# lightSource.net
KiCad netlist of a schematic drawn in EAGLE
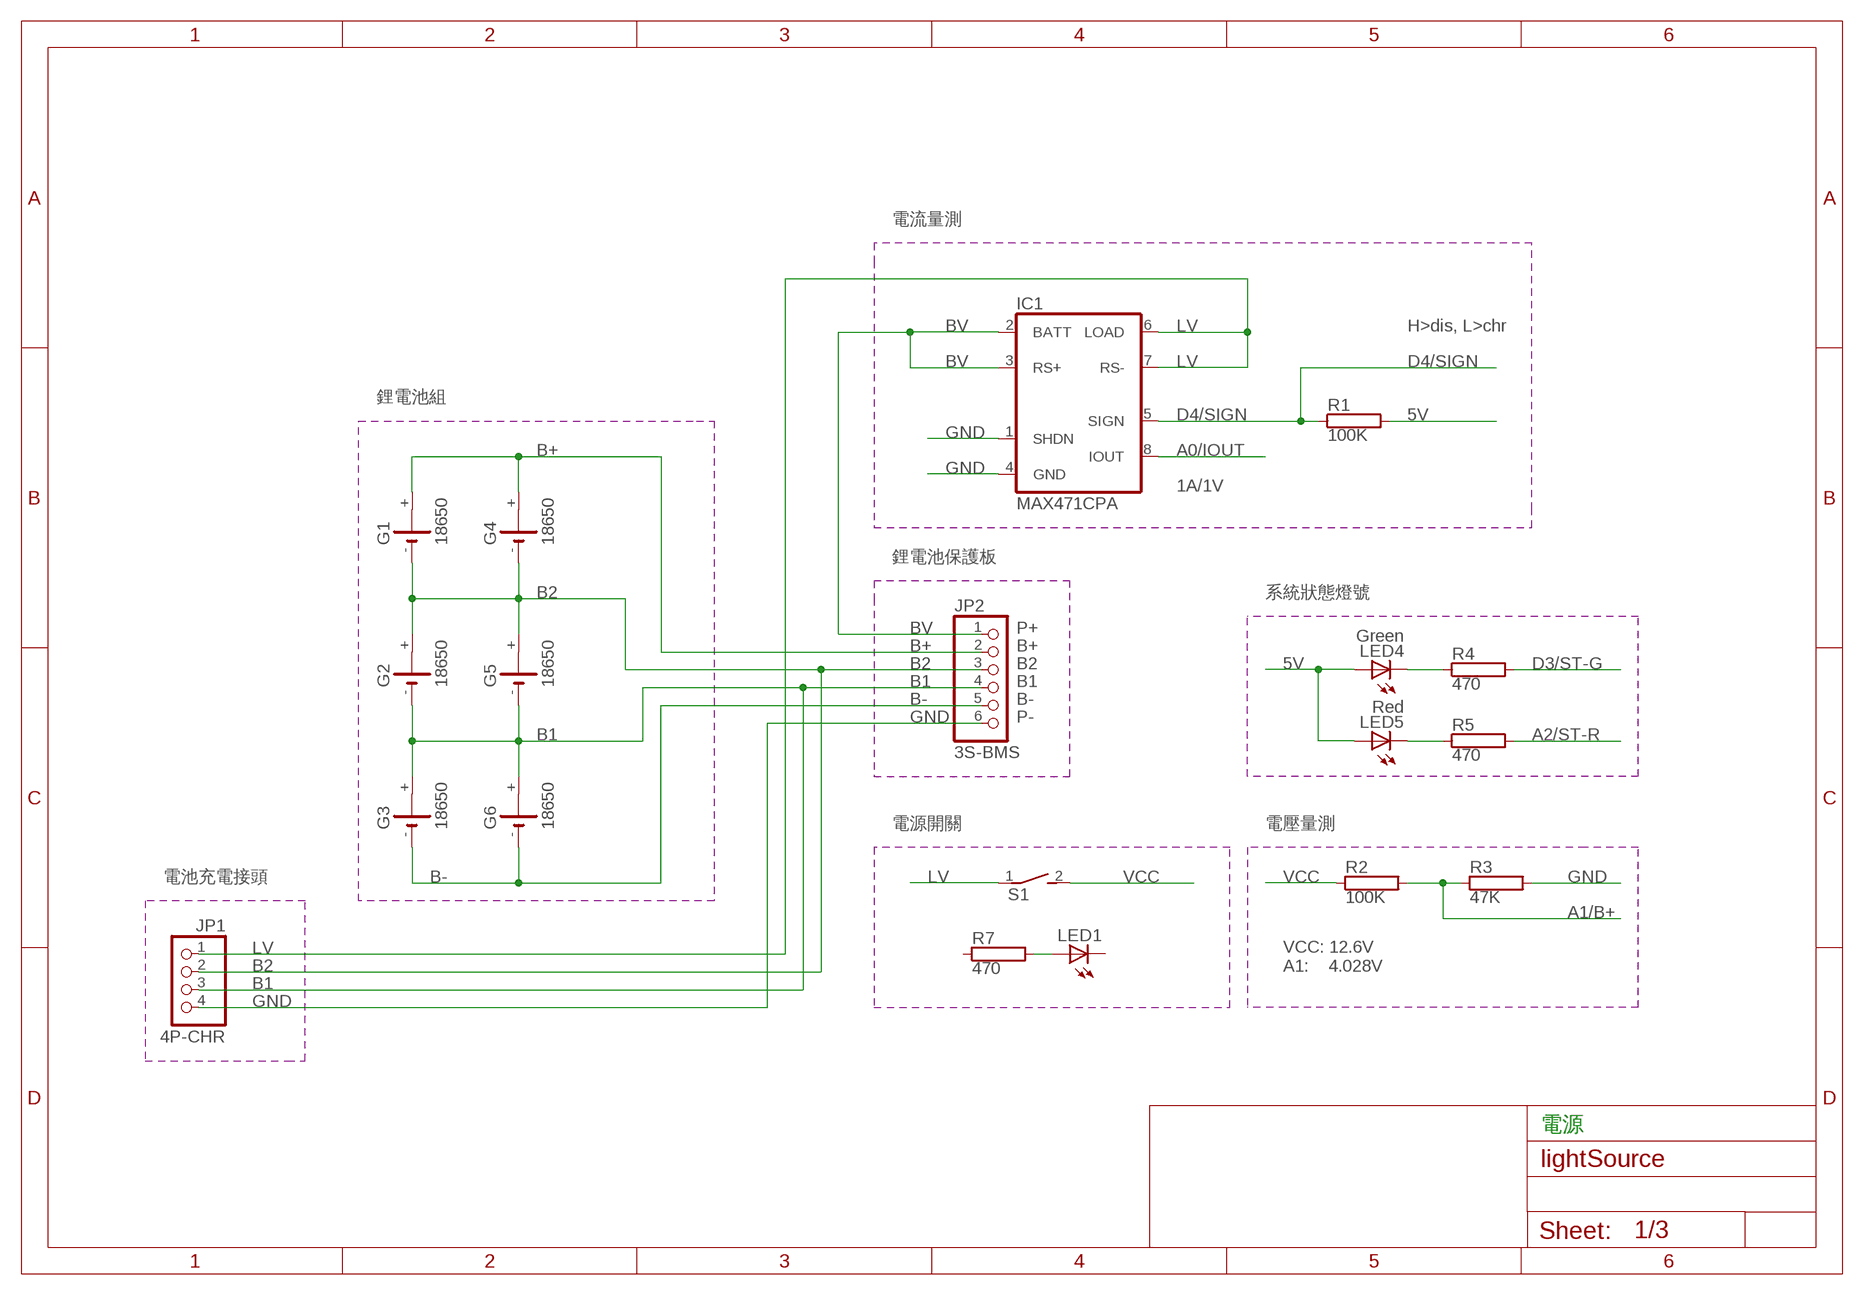
[diagram p0: schematic, sheet 1]
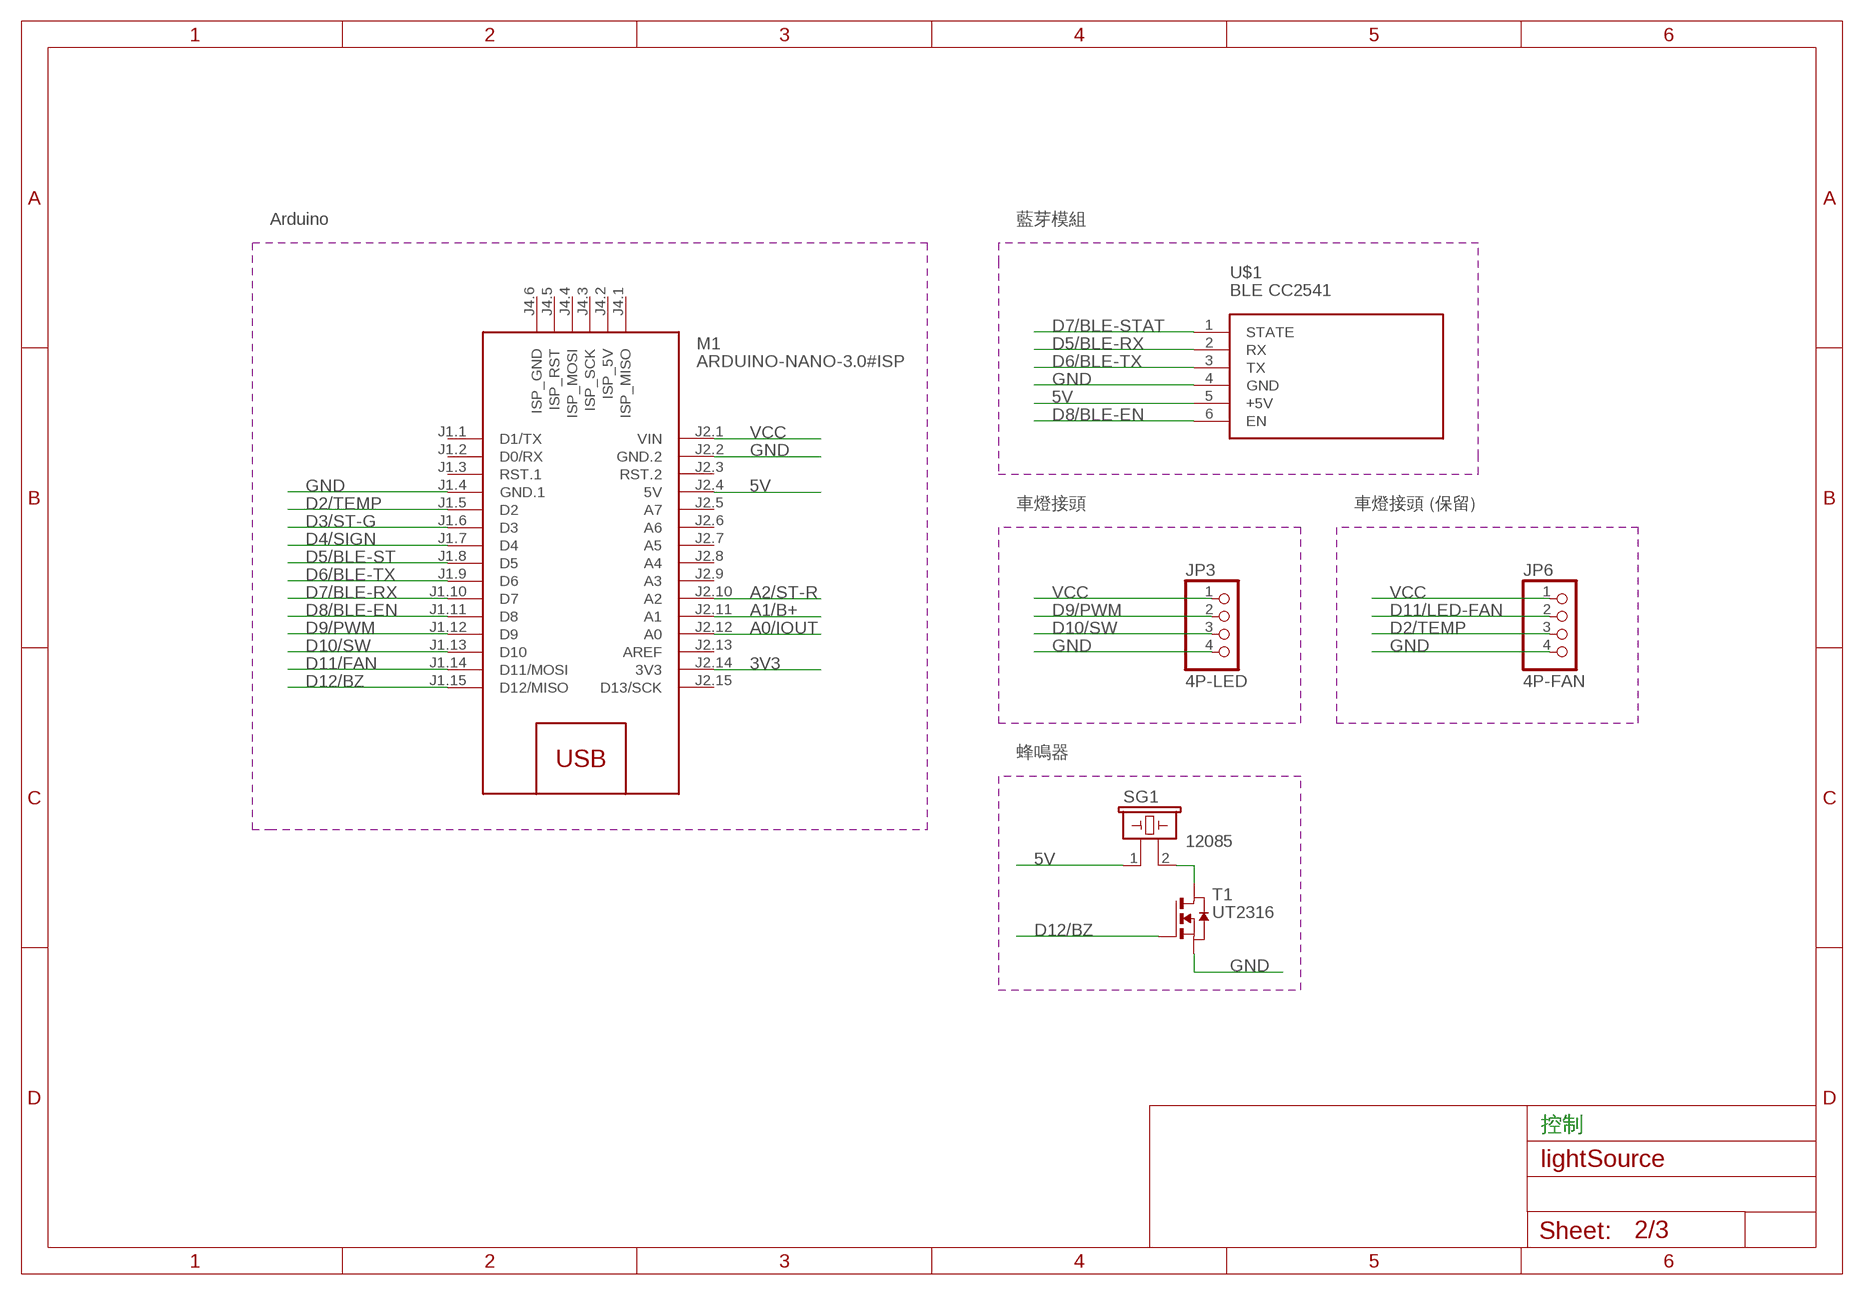
[diagram p1: schematic, sheet 2]
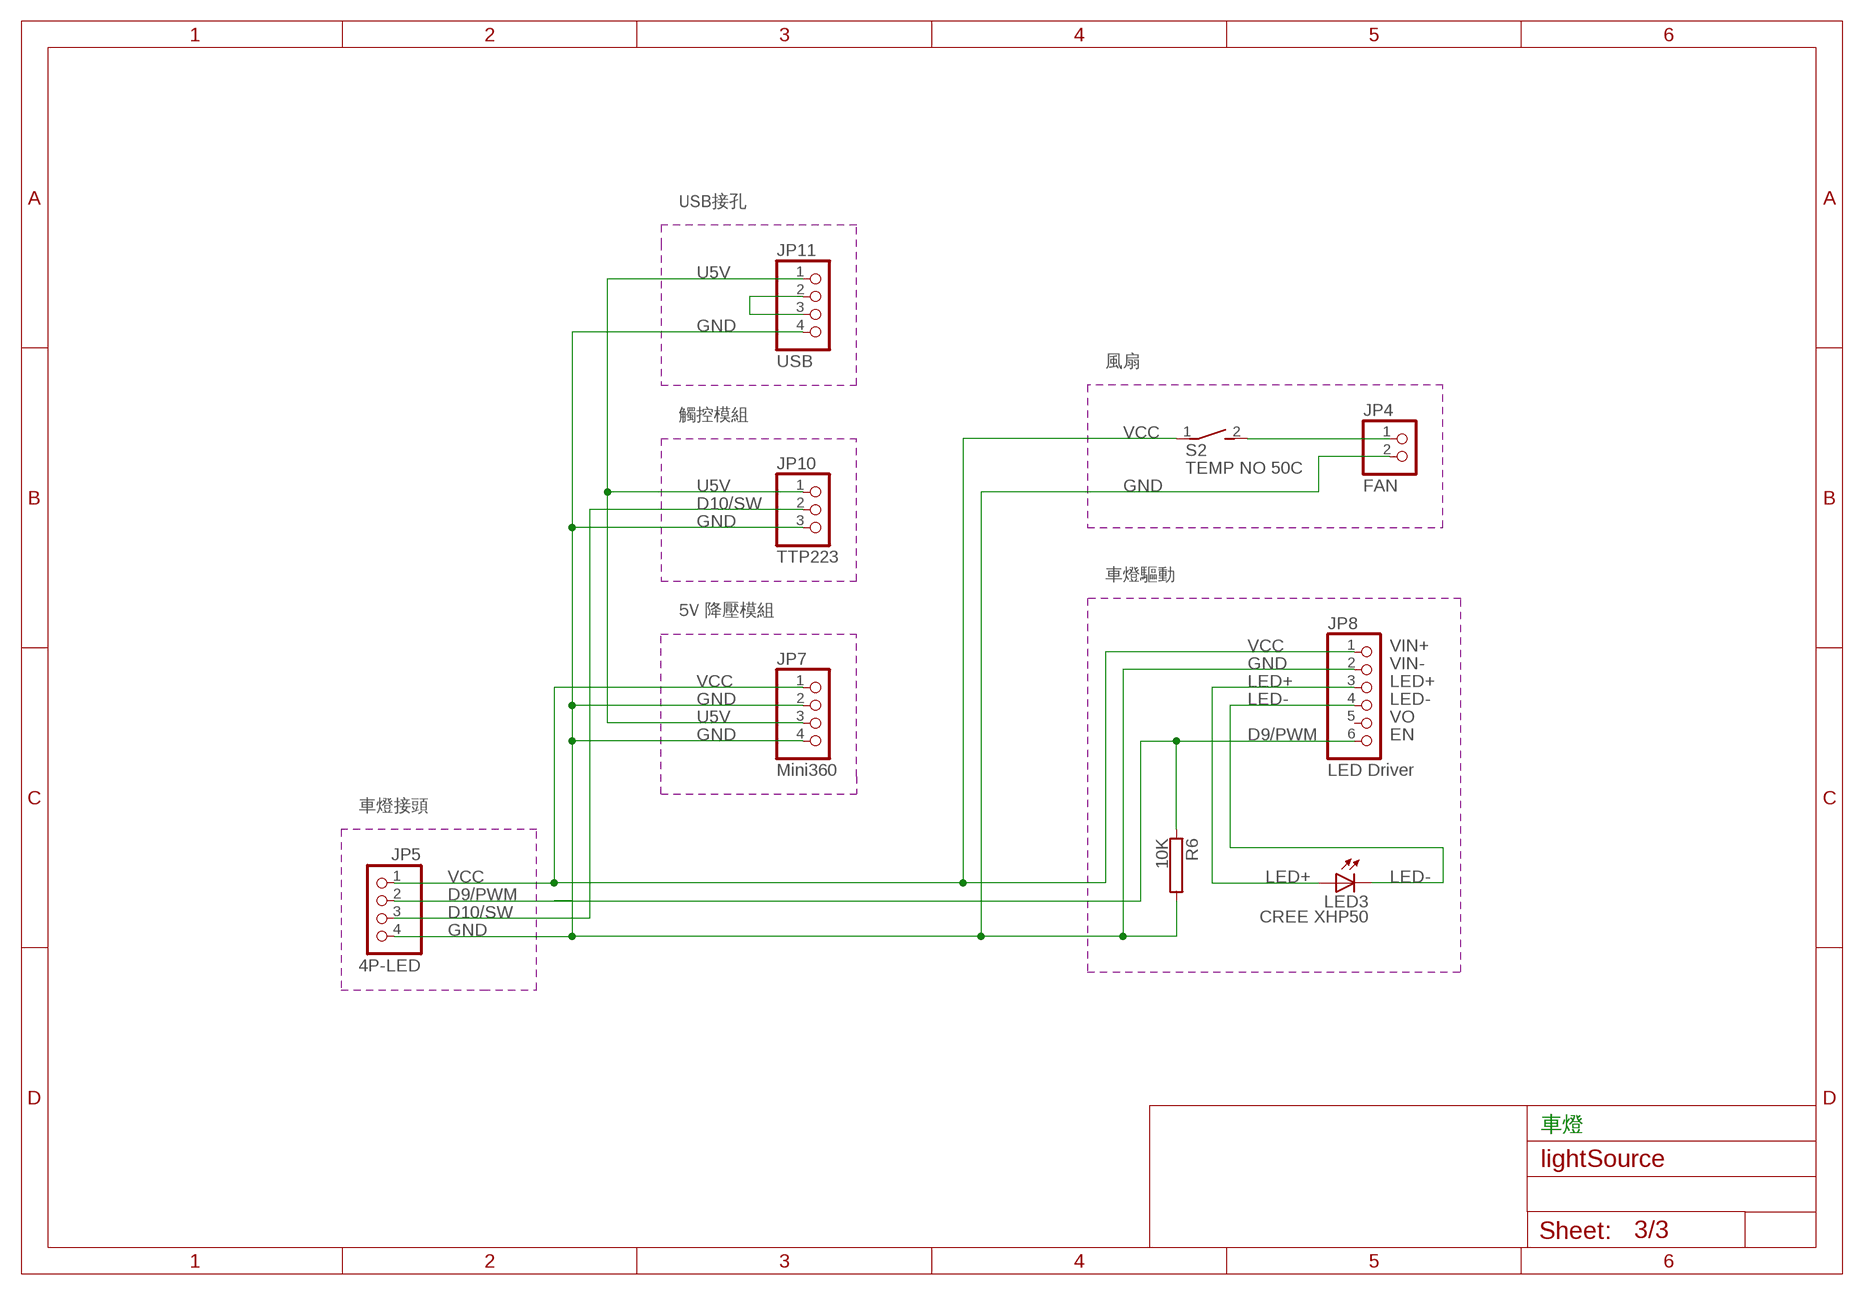
[diagram p2: schematic, sheet 3]

(export (version "E")
  (design (tool "Eeschema 10.0.6"))
  (components
    (comp (ref "JP3")
      (value "4P-LED")
      (footprint "eagle-import:1X04")
      (libsource (lib "eagle-import") (part "PINHD-1X4"))
    )
    (comp (ref "JP6")
      (value "4P-FAN")
      (footprint "eagle-import:1X04")
      (libsource (lib "eagle-import") (part "PINHD-1X4"))
    )
    (comp (ref "M1")
      (value "ARDUINO-NANO-3.0#ISP")
      (footprint "eagle-import:ARDUINO-NANO-3.0#ISP")
      (libsource (lib "eagle-import") (part "ARDUINO-NANO-3.0#ISP"))
    )
    (comp (ref "SG1")
      (value "12085")
      (footprint "eagle-import:B_C11S")
      (libsource (lib "eagle-import") (part "B/C11S"))
    )
    (comp (ref "T1")
      (value "UT2316")
      (footprint "eagle-import:SOT-23")
      (libsource (lib "eagle-import") (part "NMOSSOT23"))
    )
    (comp (ref "U$1")
      (value "BLE CC2541")
      (footprint "eagle-import:WIRELESS-BLUETOOTH-HC-05")
      (libsource (lib "eagle-import") (part "WIRELESS-BLUETOOTH-HC-05"))
    )
    (comp (ref "G1")
      (value "18650")
      (footprint "eagle-import:CRAA")
      (libsource (lib "eagle-import") (part "CRAA"))
    )
    (comp (ref "G2")
      (value "18650")
      (footprint "eagle-import:CRAA")
      (libsource (lib "eagle-import") (part "CRAA"))
    )
    (comp (ref "G3")
      (value "18650")
      (footprint "eagle-import:CRAA")
      (libsource (lib "eagle-import") (part "CRAA"))
    )
    (comp (ref "G4")
      (value "18650")
      (footprint "eagle-import:CRAA")
      (libsource (lib "eagle-import") (part "CRAA"))
    )
    (comp (ref "G5")
      (value "18650")
      (footprint "eagle-import:CRAA")
      (libsource (lib "eagle-import") (part "CRAA"))
    )
    (comp (ref "G6")
      (value "18650")
      (footprint "eagle-import:CRAA")
      (libsource (lib "eagle-import") (part "CRAA"))
    )
    (comp (ref "IC1")
      (value "MAX471CPA")
      (footprint "eagle-import:DIL08")
      (libsource (lib "eagle-import") (part "MAX471CPA"))
    )
    (comp (ref "JP1")
      (value "4P-CHR")
      (footprint "eagle-import:1X04")
      (libsource (lib "eagle-import") (part "PINHD-1X4"))
    )
    (comp (ref "JP2")
      (value "3S-BMS")
      (footprint "eagle-import:1X06")
      (libsource (lib "eagle-import") (part "PINHD-1X6"))
    )
    (comp (ref "LED1")
      (value "LED5MM")
      (footprint "eagle-import:LED5MM")
      (libsource (lib "eagle-import") (part "LED5MM"))
    )
    (comp (ref "LED4")
      (value "Green")
      (footprint "eagle-import:LED5MM")
      (libsource (lib "eagle-import") (part "LED5MM"))
    )
    (comp (ref "LED5")
      (value "Red")
      (footprint "eagle-import:LED5MM")
      (libsource (lib "eagle-import") (part "LED5MM"))
    )
    (comp (ref "R1")
      (value "100K")
      (footprint "eagle-import:RS1_4")
      (fields (field (name "MF") "OHMITE") (field (name "MPN") "RRS1K0"))
      (libsource (lib "eagle-import") (part "RRS1/4"))
    )
    (comp (ref "R2")
      (value "100K")
      (footprint "eagle-import:RS1_4")
      (fields (field (name "MF") "OHMITE") (field (name "MPN") "RRS1K0"))
      (libsource (lib "eagle-import") (part "RRS1/4"))
    )
    (comp (ref "R3")
      (value "47K")
      (footprint "eagle-import:RS1_4")
      (fields (field (name "MF") "OHMITE") (field (name "MPN") "RRS1K0"))
      (libsource (lib "eagle-import") (part "RRS1/4"))
    )
    (comp (ref "R4")
      (value "470")
      (footprint "eagle-import:RS1_4")
      (fields (field (name "MF") "OHMITE") (field (name "MPN") "RRS1K0"))
      (libsource (lib "eagle-import") (part "RRS1/4"))
    )
    (comp (ref "R5")
      (value "470")
      (footprint "eagle-import:RS1_4")
      (fields (field (name "MF") "OHMITE") (field (name "MPN") "RRS1K0"))
      (libsource (lib "eagle-import") (part "RRS1/4"))
    )
    (comp (ref "R7")
      (value "470")
      (footprint "eagle-import:RS1_4")
      (fields (field (name "MF") "OHMITE") (field (name "MPN") "RRS1K0"))
      (libsource (lib "eagle-import") (part "RRS1/4"))
    )
    (comp (ref "S1")
      (value "DS01E")
      (footprint "eagle-import:DS-01")
      (libsource (lib "eagle-import") (part "DS01E"))
    )
    (comp (ref "JP4")
      (value "FAN")
      (footprint "eagle-import:1X02")
      (libsource (lib "eagle-import") (part "PINHD-1X2"))
    )
    (comp (ref "JP5")
      (value "4P-LED")
      (footprint "eagle-import:1X04")
      (libsource (lib "eagle-import") (part "PINHD-1X4"))
    )
    (comp (ref "JP7")
      (value "Mini360")
      (footprint "eagle-import:1X04")
      (libsource (lib "eagle-import") (part "PINHD-1X4"))
    )
    (comp (ref "JP8")
      (value "LED Driver")
      (footprint "eagle-import:1X06")
      (libsource (lib "eagle-import") (part "PINHD-1X6"))
    )
    (comp (ref "JP10")
      (value "TTP223")
      (footprint "eagle-import:1X03")
      (libsource (lib "eagle-import") (part "PINHD-1X3"))
    )
    (comp (ref "JP11")
      (value "USB")
      (footprint "eagle-import:1X04")
      (libsource (lib "eagle-import") (part "PINHD-1X4"))
    )
    (comp (ref "LED3")
      (value "CREE XHP50")
      (footprint "eagle-import:LED5MM")
      (libsource (lib "eagle-import") (part "LED5MM"))
    )
    (comp (ref "R6")
      (value "10K")
      (footprint "eagle-import:RS1_4")
      (fields (field (name "MF") "OHMITE") (field (name "MPN") "RRS1K0"))
      (libsource (lib "eagle-import") (part "RRS1/4"))
    )
    (comp (ref "S2")
      (value "TEMP NO 50C")
      (footprint "eagle-import:DS-01")
      (libsource (lib "eagle-import") (part "DS01E"))
    )
  )
  (nets
    (net (code "1") (name "3V3") (class "Default")
      (node (ref "M1") (pin "J2.14") (pinfunction "3V3_J2.14") (pintype "power_in"))
    )
    (net (code "2") (name "5V") (class "Default")
      (node (ref "LED4") (pin "A") (pinfunction "A_A") (pintype "passive"))
      (node (ref "LED5") (pin "A") (pinfunction "A_A") (pintype "passive"))
      (node (ref "M1") (pin "J2.4") (pinfunction "5V_J2.4") (pintype "power_in"))
      (node (ref "R1") (pin "2") (pinfunction "2_2") (pintype "passive"))
      (node (ref "SG1") (pin "1") (pinfunction "1_1") (pintype "passive"))
      (node (ref "U$1") (pin "5") (pinfunction "+5V_5") (pintype "power_in"))
    )
    (net (code "3") (name "A0{slash}IOUT") (class "Default")
      (node (ref "IC1") (pin "8") (pinfunction "IOUT_8") (pintype "output"))
      (node (ref "M1") (pin "J2.12") (pinfunction "A0_J2.12") (pintype "bidirectional"))
    )
    (net (code "4") (name "A1{slash}B+") (class "Default")
      (node (ref "M1") (pin "J2.11") (pinfunction "A1_J2.11") (pintype "bidirectional"))
      (node (ref "R2") (pin "2") (pinfunction "2_2") (pintype "passive"))
      (node (ref "R3") (pin "1") (pinfunction "1_1") (pintype "passive"))
    )
    (net (code "5") (name "A2{slash}ST-R") (class "Default")
      (node (ref "M1") (pin "J2.10") (pinfunction "A2_J2.10") (pintype "bidirectional"))
      (node (ref "R5") (pin "2") (pinfunction "2_2") (pintype "passive"))
    )
    (net (code "6") (name "B+") (class "Default")
      (node (ref "G1") (pin "+") (pinfunction "+_+") (pintype "passive"))
      (node (ref "G4") (pin "+") (pinfunction "+_+") (pintype "passive"))
      (node (ref "JP2") (pin "2") (pinfunction "2_2") (pintype "passive"))
    )
    (net (code "7") (name "B-") (class "Default")
      (node (ref "G3") (pin "-") (pinfunction "-_-") (pintype "passive"))
      (node (ref "G6") (pin "-") (pinfunction "-_-") (pintype "passive"))
      (node (ref "JP2") (pin "5") (pinfunction "5_5") (pintype "passive"))
    )
    (net (code "8") (name "B1") (class "Default")
      (node (ref "G2") (pin "-") (pinfunction "-_-") (pintype "passive"))
      (node (ref "G3") (pin "+") (pinfunction "+_+") (pintype "passive"))
      (node (ref "G5") (pin "-") (pinfunction "-_-") (pintype "passive"))
      (node (ref "G6") (pin "+") (pinfunction "+_+") (pintype "passive"))
      (node (ref "JP1") (pin "3") (pinfunction "3_3") (pintype "passive"))
      (node (ref "JP2") (pin "4") (pinfunction "4_4") (pintype "passive"))
    )
    (net (code "9") (name "B2") (class "Default")
      (node (ref "G1") (pin "-") (pinfunction "-_-") (pintype "passive"))
      (node (ref "G2") (pin "+") (pinfunction "+_+") (pintype "passive"))
      (node (ref "G4") (pin "-") (pinfunction "-_-") (pintype "passive"))
      (node (ref "G5") (pin "+") (pinfunction "+_+") (pintype "passive"))
      (node (ref "JP1") (pin "2") (pinfunction "2_2") (pintype "passive"))
      (node (ref "JP2") (pin "3") (pinfunction "3_3") (pintype "passive"))
    )
    (net (code "10") (name "BV") (class "Default")
      (node (ref "IC1") (pin "2") (pinfunction "BATT_2") (pintype "input"))
      (node (ref "IC1") (pin "3") (pinfunction "RS+_3") (pintype "input"))
      (node (ref "JP2") (pin "1") (pinfunction "1_1") (pintype "passive"))
    )
    (net (code "11") (name "D2{slash}TEMP") (class "Default")
      (node (ref "JP6") (pin "3") (pinfunction "3_3") (pintype "passive"))
      (node (ref "M1") (pin "J1.5") (pinfunction "D2_J1.5") (pintype "bidirectional"))
    )
    (net (code "12") (name "D3{slash}ST-G") (class "Default")
      (node (ref "M1") (pin "J1.6") (pinfunction "D3_J1.6") (pintype "bidirectional"))
      (node (ref "R4") (pin "2") (pinfunction "2_2") (pintype "passive"))
    )
    (net (code "13") (name "D4{slash}SIGN") (class "Default")
      (node (ref "IC1") (pin "5") (pinfunction "SIGN_5") (pintype "open_collector"))
      (node (ref "M1") (pin "J1.7") (pinfunction "D4_J1.7") (pintype "bidirectional"))
      (node (ref "R1") (pin "1") (pinfunction "1_1") (pintype "passive"))
    )
    (net (code "14") (name "D5{slash}BLE-RX") (class "Default")
      (node (ref "U$1") (pin "2") (pinfunction "RX_2") (pintype "bidirectional"))
    )
    (net (code "15") (name "D5{slash}BLE-ST") (class "Default")
      (node (ref "M1") (pin "J1.8") (pinfunction "D5_J1.8") (pintype "bidirectional"))
    )
    (net (code "16") (name "D6{slash}BLE-TX") (class "Default")
      (node (ref "M1") (pin "J1.9") (pinfunction "D6_J1.9") (pintype "bidirectional"))
      (node (ref "U$1") (pin "3") (pinfunction "TX_3") (pintype "bidirectional"))
    )
    (net (code "17") (name "D7{slash}BLE-RX") (class "Default")
      (node (ref "M1") (pin "J1.10") (pinfunction "D7_J1.10") (pintype "bidirectional"))
    )
    (net (code "18") (name "D7{slash}BLE-STAT") (class "Default")
      (node (ref "U$1") (pin "1") (pinfunction "STATE_1") (pintype "bidirectional"))
    )
    (net (code "19") (name "D8{slash}BLE-EN") (class "Default")
      (node (ref "M1") (pin "J1.11") (pinfunction "D8_J1.11") (pintype "bidirectional"))
      (node (ref "U$1") (pin "6") (pinfunction "EN_6") (pintype "bidirectional"))
    )
    (net (code "20") (name "D9{slash}PWM") (class "Default")
      (node (ref "JP3") (pin "2") (pinfunction "2_2") (pintype "passive"))
      (node (ref "JP5") (pin "2") (pinfunction "2_2") (pintype "passive"))
      (node (ref "JP8") (pin "6") (pinfunction "6_6") (pintype "passive"))
      (node (ref "M1") (pin "J1.12") (pinfunction "D9_J1.12") (pintype "bidirectional"))
      (node (ref "R6") (pin "1") (pinfunction "1_1") (pintype "passive"))
    )
    (net (code "21") (name "D10{slash}SW") (class "Default")
      (node (ref "JP10") (pin "2") (pinfunction "2_2") (pintype "passive"))
      (node (ref "JP3") (pin "3") (pinfunction "3_3") (pintype "passive"))
      (node (ref "JP5") (pin "3") (pinfunction "3_3") (pintype "passive"))
      (node (ref "M1") (pin "J1.13") (pinfunction "D10_J1.13") (pintype "bidirectional"))
    )
    (net (code "22") (name "D11{slash}FAN") (class "Default")
      (node (ref "M1") (pin "J1.14") (pinfunction "D11/MOSI_J1.14") (pintype "bidirectional"))
    )
    (net (code "23") (name "D11{slash}LED-FAN") (class "Default")
      (node (ref "JP6") (pin "2") (pinfunction "2_2") (pintype "passive"))
    )
    (net (code "24") (name "D12{slash}BZ") (class "Default")
      (node (ref "M1") (pin "J1.15") (pinfunction "D12/MISO_J1.15") (pintype "bidirectional"))
      (node (ref "T1") (pin "3") (pinfunction "G_3") (pintype "passive"))
    )
    (net (code "25") (name "GND") (class "Default")
      (node (ref "IC1") (pin "1") (pinfunction "SHDN_1") (pintype "input"))
      (node (ref "IC1") (pin "4") (pinfunction "GND_4") (pintype "power_in"))
      (node (ref "JP1") (pin "4") (pinfunction "4_4") (pintype "passive"))
      (node (ref "JP10") (pin "3") (pinfunction "3_3") (pintype "passive"))
      (node (ref "JP11") (pin "4") (pinfunction "4_4") (pintype "passive"))
      (node (ref "JP2") (pin "6") (pinfunction "6_6") (pintype "passive"))
      (node (ref "JP3") (pin "4") (pinfunction "4_4") (pintype "passive"))
      (node (ref "JP4") (pin "2") (pinfunction "2_2") (pintype "passive"))
      (node (ref "JP5") (pin "4") (pinfunction "4_4") (pintype "passive"))
      (node (ref "JP6") (pin "4") (pinfunction "4_4") (pintype "passive"))
      (node (ref "JP7") (pin "2") (pinfunction "2_2") (pintype "passive"))
      (node (ref "JP7") (pin "4") (pinfunction "4_4") (pintype "passive"))
      (node (ref "JP8") (pin "2") (pinfunction "2_2") (pintype "passive"))
      (node (ref "M1") (pin "J1.4") (pinfunction "GND.1_J1.4") (pintype "power_in"))
      (node (ref "M1") (pin "J2.2") (pinfunction "GND.2_J2.2") (pintype "power_in"))
      (node (ref "R3") (pin "2") (pinfunction "2_2") (pintype "passive"))
      (node (ref "R6") (pin "2") (pinfunction "2_2") (pintype "passive"))
      (node (ref "T1") (pin "2") (pinfunction "S_2") (pintype "passive"))
      (node (ref "U$1") (pin "4") (pinfunction "GND_4") (pintype "power_in"))
    )
    (net (code "26") (name "LED+") (class "Default")
      (node (ref "JP8") (pin "3") (pinfunction "3_3") (pintype "passive"))
      (node (ref "LED3") (pin "A") (pinfunction "A_A") (pintype "passive"))
    )
    (net (code "27") (name "LED-") (class "Default")
      (node (ref "JP8") (pin "4") (pinfunction "4_4") (pintype "passive"))
      (node (ref "LED3") (pin "K") (pinfunction "C_K") (pintype "passive"))
    )
    (net (code "28") (name "LV") (class "Default")
      (node (ref "IC1") (pin "6") (pinfunction "LOAD_6") (pintype "output"))
      (node (ref "IC1") (pin "7") (pinfunction "RS-_7") (pintype "input"))
      (node (ref "JP1") (pin "1") (pinfunction "1_1") (pintype "passive"))
      (node (ref "S1") (pin "1") (pinfunction "1_1") (pintype "passive"))
    )
    (net (code "29") (name "Net-(JP4-Pad1)") (class "Default")
      (node (ref "JP4") (pin "1") (pinfunction "1_1") (pintype "passive"))
      (node (ref "S2") (pin "2") (pinfunction "2_2") (pintype "passive"))
    )
    (net (code "30") (name "Net-(JP11-Pad2)") (class "Default")
      (node (ref "JP11") (pin "2") (pinfunction "2_2") (pintype "passive"))
      (node (ref "JP11") (pin "3") (pinfunction "3_3") (pintype "passive"))
    )
    (net (code "31") (name "Net-(LED1-PadA)") (class "Default")
      (node (ref "LED1") (pin "A") (pinfunction "A_A") (pintype "passive"))
      (node (ref "R7") (pin "2") (pinfunction "2_2") (pintype "passive"))
    )
    (net (code "32") (name "Net-(LED4-C)") (class "Default")
      (node (ref "LED4") (pin "K") (pinfunction "C_K") (pintype "passive"))
      (node (ref "R4") (pin "1") (pinfunction "1_1") (pintype "passive"))
    )
    (net (code "33") (name "Net-(LED5-C)") (class "Default")
      (node (ref "LED5") (pin "K") (pinfunction "C_K") (pintype "passive"))
      (node (ref "R5") (pin "1") (pinfunction "1_1") (pintype "passive"))
    )
    (net (code "34") (name "Net-(T1-D)") (class "Default")
      (node (ref "SG1") (pin "2") (pinfunction "2_2") (pintype "passive"))
      (node (ref "T1") (pin "1") (pinfunction "D_1") (pintype "passive"))
    )
    (net (code "35") (name "U5V") (class "Default")
      (node (ref "JP10") (pin "1") (pinfunction "1_1") (pintype "passive"))
      (node (ref "JP11") (pin "1") (pinfunction "1_1") (pintype "passive"))
      (node (ref "JP7") (pin "3") (pinfunction "3_3") (pintype "passive"))
    )
    (net (code "36") (name "VCC") (class "Default")
      (node (ref "JP3") (pin "1") (pinfunction "1_1") (pintype "passive"))
      (node (ref "JP5") (pin "1") (pinfunction "1_1") (pintype "passive"))
      (node (ref "JP6") (pin "1") (pinfunction "1_1") (pintype "passive"))
      (node (ref "JP7") (pin "1") (pinfunction "1_1") (pintype "passive"))
      (node (ref "JP8") (pin "1") (pinfunction "1_1") (pintype "passive"))
      (node (ref "M1") (pin "J2.1") (pinfunction "VIN_J2.1") (pintype "power_in"))
      (node (ref "R2") (pin "1") (pinfunction "1_1") (pintype "passive"))
      (node (ref "S1") (pin "2") (pinfunction "2_2") (pintype "passive"))
      (node (ref "S2") (pin "1") (pinfunction "1_1") (pintype "passive"))
    )
    (net (code "37") (name "unconnected-(G1-+-Pad+@1)") (class "Default")
      (node (ref "G1") (pin "+@1") (pinfunction "+_+@1") (pintype "passive"))
    )
    (net (code "38") (name "unconnected-(G2-+-Pad+@1)") (class "Default")
      (node (ref "G2") (pin "+@1") (pinfunction "+_+@1") (pintype "passive"))
    )
    (net (code "39") (name "unconnected-(G3-+-Pad+@1)") (class "Default")
      (node (ref "G3") (pin "+@1") (pinfunction "+_+@1") (pintype "passive"))
    )
    (net (code "40") (name "unconnected-(G4-+-Pad+@1)") (class "Default")
      (node (ref "G4") (pin "+@1") (pinfunction "+_+@1") (pintype "passive"))
    )
    (net (code "41") (name "unconnected-(G5-+-Pad+@1)") (class "Default")
      (node (ref "G5") (pin "+@1") (pinfunction "+_+@1") (pintype "passive"))
    )
    (net (code "42") (name "unconnected-(G6-+-Pad+@1)") (class "Default")
      (node (ref "G6") (pin "+@1") (pinfunction "+_+@1") (pintype "passive"))
    )
    (net (code "43") (name "unconnected-(JP8-Pad5)") (class "Default")
      (node (ref "JP8") (pin "5") (pinfunction "5_5") (pintype "passive"))
    )
    (net (code "44") (name "unconnected-(LED1-C-PadK)") (class "Default")
      (node (ref "LED1") (pin "K") (pinfunction "C_K") (pintype "passive"))
    )
    (net (code "45") (name "unconnected-(M1-A3-PadJ2.9)") (class "Default")
      (node (ref "M1") (pin "J2.9") (pinfunction "A3_J2.9") (pintype "bidirectional"))
    )
    (net (code "46") (name "unconnected-(M1-A4-PadJ2.8)") (class "Default")
      (node (ref "M1") (pin "J2.8") (pinfunction "A4_J2.8") (pintype "bidirectional"))
    )
    (net (code "47") (name "unconnected-(M1-A5-PadJ2.7)") (class "Default")
      (node (ref "M1") (pin "J2.7") (pinfunction "A5_J2.7") (pintype "bidirectional"))
    )
    (net (code "48") (name "unconnected-(M1-A6-PadJ2.6)") (class "Default")
      (node (ref "M1") (pin "J2.6") (pinfunction "A6_J2.6") (pintype "bidirectional"))
    )
    (net (code "49") (name "unconnected-(M1-A7-PadJ2.5)") (class "Default")
      (node (ref "M1") (pin "J2.5") (pinfunction "A7_J2.5") (pintype "bidirectional"))
    )
    (net (code "50") (name "unconnected-(M1-AREF-PadJ2.13)") (class "Default")
      (node (ref "M1") (pin "J2.13") (pinfunction "AREF_J2.13") (pintype "bidirectional"))
    )
    (net (code "51") (name "unconnected-(M1-D0{slash}RX-PadJ1.2)") (class "Default")
      (node (ref "M1") (pin "J1.2") (pinfunction "D0/RX_J1.2") (pintype "bidirectional"))
    )
    (net (code "52") (name "unconnected-(M1-D1{slash}TX-PadJ1.1)") (class "Default")
      (node (ref "M1") (pin "J1.1") (pinfunction "D1/TX_J1.1") (pintype "bidirectional"))
    )
    (net (code "53") (name "unconnected-(M1-D13{slash}SCK-PadJ2.15)") (class "Default")
      (node (ref "M1") (pin "J2.15") (pinfunction "D13/SCK_J2.15") (pintype "bidirectional"))
    )
    (net (code "54") (name "unconnected-(M1-ISP_5V-PadJ4.2)") (class "Default")
      (node (ref "M1") (pin "J4.2") (pinfunction "ISP_5V_J4.2") (pintype "bidirectional"))
    )
    (net (code "55") (name "unconnected-(M1-ISP_GND-PadJ4.6)") (class "Default")
      (node (ref "M1") (pin "J4.6") (pinfunction "ISP_GND_J4.6") (pintype "bidirectional"))
    )
    (net (code "56") (name "unconnected-(M1-ISP_MISO-PadJ4.1)") (class "Default")
      (node (ref "M1") (pin "J4.1") (pinfunction "ISP_MISO_J4.1") (pintype "bidirectional"))
    )
    (net (code "57") (name "unconnected-(M1-ISP_MOSI-PadJ4.4)") (class "Default")
      (node (ref "M1") (pin "J4.4") (pinfunction "ISP_MOSI_J4.4") (pintype "bidirectional"))
    )
    (net (code "58") (name "unconnected-(M1-ISP_RST-PadJ4.5)") (class "Default")
      (node (ref "M1") (pin "J4.5") (pinfunction "ISP_RST_J4.5") (pintype "bidirectional"))
    )
    (net (code "59") (name "unconnected-(M1-ISP_SCK-PadJ4.3)") (class "Default")
      (node (ref "M1") (pin "J4.3") (pinfunction "ISP_SCK_J4.3") (pintype "bidirectional"))
    )
    (net (code "60") (name "unconnected-(M1-RST.1-PadJ1.3)") (class "Default")
      (node (ref "M1") (pin "J1.3") (pinfunction "RST.1_J1.3") (pintype "bidirectional"))
    )
    (net (code "61") (name "unconnected-(M1-RST.2-PadJ2.3)") (class "Default")
      (node (ref "M1") (pin "J2.3") (pinfunction "RST.2_J2.3") (pintype "bidirectional"))
    )
    (net (code "62") (name "unconnected-(R7-Pad1)") (class "Default")
      (node (ref "R7") (pin "1") (pinfunction "1_1") (pintype "passive"))
    )
  )
)
